# POWER.net
KiCad netlist of a schematic drawn in Altium Designer
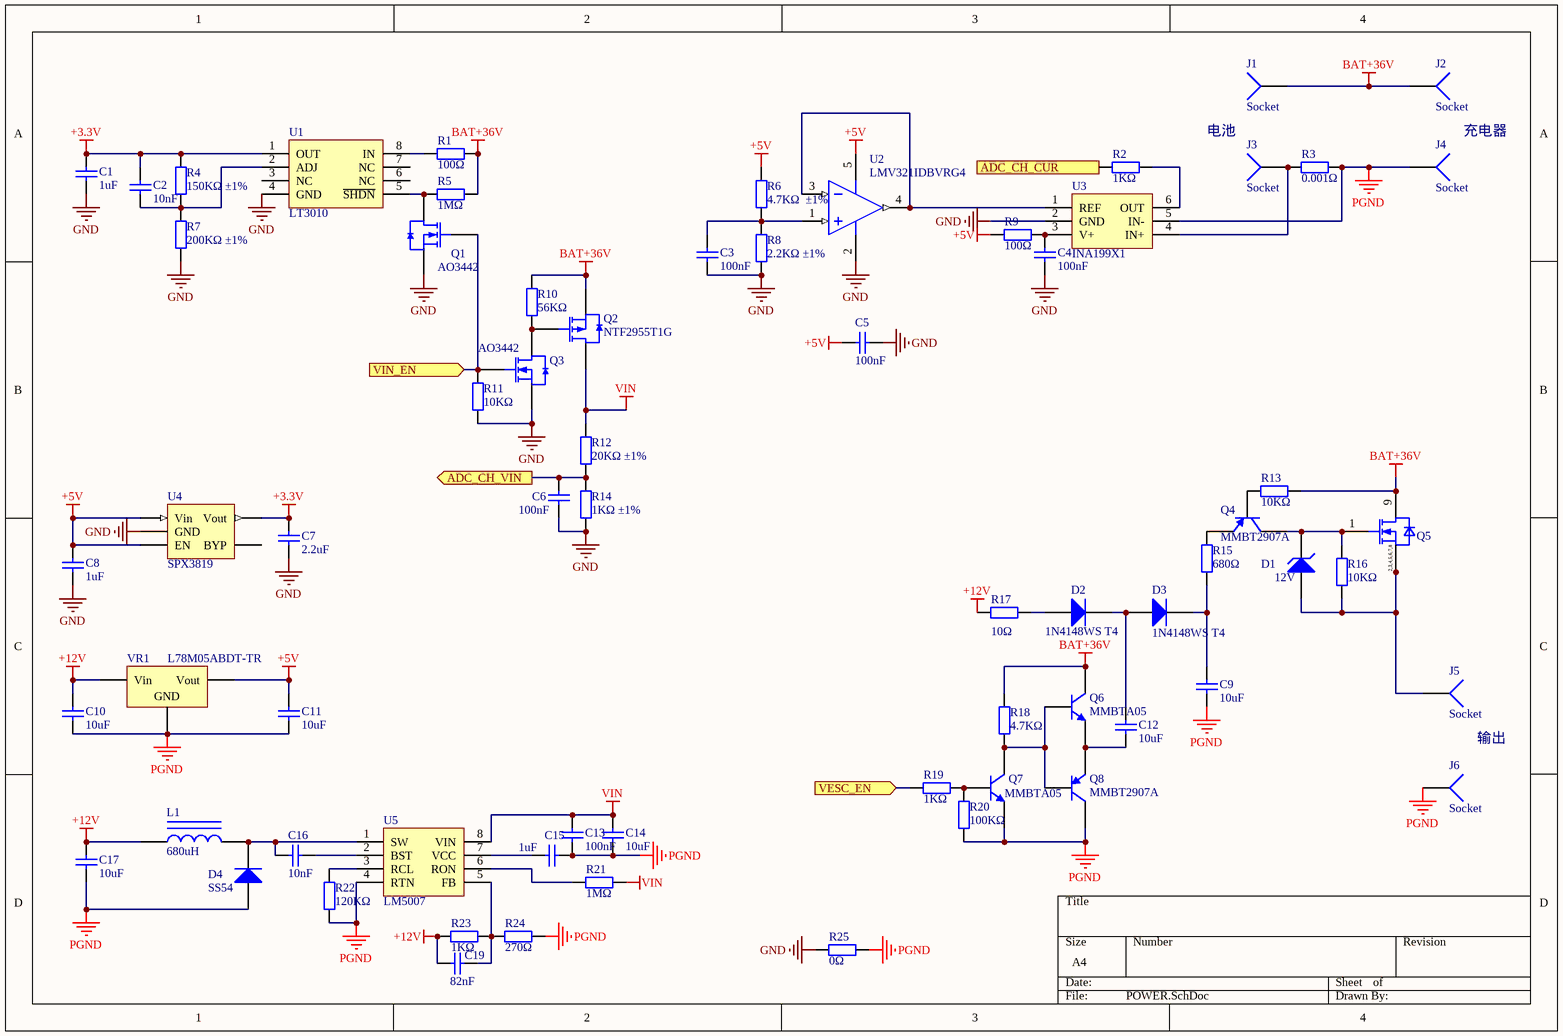
[diagram p0: POWER.SchDoc]

(export (version "E")
  (design (tool "Eeschema 10.0.6"))
  (components
    (comp (ref "C1")
      (value "1uF")
      (footprint "0603_C")
      (description "贴片电容")
      (libsource (lib "altium-import") (part "root_1_0603 1uF (105) 10% 50V_"))
    )
    (comp (ref "C2")
      (value "10nF")
      (footprint "0402_C")
      (description "贴片电容")
      (libsource (lib "Miscellaneous Devices LC") (part "0402 10nF (103) 10% 50V"))
    )
    (comp (ref "C3")
      (value "100nF")
      (footprint "0402_C")
      (description "贴片电容")
      (libsource (lib "Miscellaneous Devices LC") (part "0402 100nF (104) 10% 16V"))
    )
    (comp (ref "C4")
      (value "100nF")
      (footprint "0402_C")
      (description "贴片电容")
      (libsource (lib "Miscellaneous Devices LC") (part "0402 100nF (104) 10% 16V"))
    )
    (comp (ref "C5")
      (value "100nF")
      (footprint "0402_C")
      (description "贴片电容")
      (libsource (lib "Miscellaneous Devices LC") (part "0402 100nF (104) 10% 16V"))
    )
    (comp (ref "C6")
      (value "100nF")
      (footprint "0402_C")
      (description "贴片电容")
      (libsource (lib "Miscellaneous Devices LC") (part "0402 100nF (104) 10% 16V"))
    )
    (comp (ref "C7")
      (value "2.2uF")
      (footprint "0603_C")
      (description "贴片电容")
      (libsource (lib "altium-import") (part "root_1_0603 2.2uF (225) 10% 16V_"))
    )
    (comp (ref "C8")
      (value "1uF")
      (footprint "0603_C")
      (description "贴片电容")
      (libsource (lib "altium-import") (part "root_1_0603 1uF (105) 10% 50V_"))
    )
    (comp (ref "C9")
      (value "10uF")
      (footprint "0805_C")
      (description "贴片电容")
      (libsource (lib "Miscellaneous Devices LC") (part "0805 10uF (106) 10% 25V"))
    )
    (comp (ref "C10")
      (value "10uF")
      (footprint "0805_C")
      (description "贴片电容")
      (libsource (lib "Miscellaneous Devices LC") (part "0805 10uF (106) 10% 25V"))
    )
    (comp (ref "C11")
      (value "10uF")
      (footprint "0805_C")
      (description "贴片电容")
      (libsource (lib "Miscellaneous Devices LC") (part "0805 10uF (106) 10% 25V"))
    )
    (comp (ref "C12")
      (value "10uF")
      (footprint "0805_C")
      (description "贴片电容")
      (libsource (lib "Miscellaneous Devices LC") (part "0805 10uF (106) 10% 25V"))
    )
    (comp (ref "C13")
      (value "100nF")
      (footprint "0805_C")
      (description "贴片电容")
      (libsource (lib "altium-import") (part "root_1_0805 100nF(104) 10% 50V_"))
    )
    (comp (ref "C14")
      (value "10uF")
      (footprint "1206_C")
      (description "贴片电容")
      (libsource (lib "Miscellaneous Devices LC") (part "1206 10uF (106) 10% 50V"))
    )
    (comp (ref "C15")
      (value "1uF")
      (footprint "0402_C")
      (description "贴片电容")
      (libsource (lib "altium-import") (part "root_0_0603 1uF (105) 10% 50V_"))
    )
    (comp (ref "C16")
      (value "10nF")
      (footprint "0603_C")
      (description "贴片电容")
      (libsource (lib "Miscellaneous Devices LC") (part "0603 10nF (103) 10% 50V"))
    )
    (comp (ref "C17")
      (value "10uF")
      (footprint "1206_C")
      (description "贴片电容")
      (libsource (lib "Miscellaneous Devices LC") (part "1206 10uF (106) 10% 50V"))
    )
    (comp (ref "C19")
      (value "82nF")
      (footprint "0402_C")
      (description "贴片电容")
      (libsource (lib "altium-import") (part "root_0_0603 82pF (820) 5% 50V_"))
    )
    (comp (ref "D1")
      (value "12V")
      (footprint "LL-34")
      (description "稳压二极管")
      (libsource (lib "Miscellaneous Devices LC") (part "LL-34 ZMM5V6"))
    )
    (comp (ref "D2")
      (value "1N4148WS T4")
      (footprint "SOD-323")
      (description "二极管")
      (libsource (lib "Miscellaneous Devices LC") (part "SOD-323 1N4148WS T4"))
    )
    (comp (ref "D3")
      (value "1N4148WS T4")
      (footprint "SOD-323")
      (description "二极管")
      (libsource (lib "Miscellaneous Devices LC") (part "SOD-323 1N4148WS T4"))
    )
    (comp (ref "D4")
      (value "SS54")
      (footprint "SMA(DO-214AC)_S1")
      (description "二极管")
      (libsource (lib "altium-import") (part "root_1_SMA(DO-214AC) SS54_"))
    )
    (comp (ref "J1")
      (value "Socket")
      (footprint "PIN1")
      (fields (field (name "PUBLISHER") "Altium Limited"))
      (libsource (lib "Miscellaneous Connectors") (part "Socket"))
    )
    (comp (ref "J2")
      (value "Socket")
      (footprint "PIN1")
      (fields (field (name "PUBLISHER") "Altium Limited"))
      (libsource (lib "Miscellaneous Connectors") (part "Socket"))
    )
    (comp (ref "J3")
      (value "Socket")
      (footprint "PIN1")
      (fields (field (name "PUBLISHER") "Altium Limited"))
      (libsource (lib "Miscellaneous Connectors") (part "Socket"))
    )
    (comp (ref "J4")
      (value "Socket")
      (footprint "PIN1")
      (fields (field (name "PUBLISHER") "Altium Limited"))
      (libsource (lib "Miscellaneous Connectors") (part "Socket"))
    )
    (comp (ref "J5")
      (value "Socket")
      (footprint "PIN1")
      (fields (field (name "PUBLISHER") "Altium Limited"))
      (libsource (lib "Miscellaneous Connectors") (part "Socket"))
    )
    (comp (ref "J6")
      (value "Socket")
      (footprint "PIN1")
      (fields (field (name "PUBLISHER") "Altium Limited"))
      (libsource (lib "Miscellaneous Connectors") (part "Socket"))
    )
    (comp (ref "L1")
      (value "680uH")
      (footprint "CDRH74")
      (description "贴片电感")
      (libsource (lib "Miscellaneous Devices LC") (part "0805 10uH 10%"))
    )
    (comp (ref "Q1")
      (value "AO3442")
      (footprint "SOT-23-3L")
      (description "MOS(场效应管)")
      (libsource (lib "altium-import") (part "root_0_mirrored_AO3400A N道沟 X0YV1T SOT-23_"))
    )
    (comp (ref "Q2")
      (value "NTF2955T1G")
      (footprint "SOT-223")
      (description "MOS(场效应管)")
      (libsource (lib "altium-import") (part "root_2_mirrored_AO3401A P道沟 X13A15 SOT-23_"))
    )
    (comp (ref "Q3")
      (value "AO3442")
      (footprint "SOT-23-3L")
      (description "MOS(场效应管)")
      (libsource (lib "altium-import") (part "root_0_AO3400A N道沟 X0YV1T SOT-23_"))
    )
    (comp (ref "Q4")
      (value "MMBT2907A")
      (footprint "SOT-23(SOT-23-3)")
      (description "三极管")
      (libsource (lib "Miscellaneous Devices LC") (part "SOT-23 SS8550 Y2"))
    )
    (comp (ref "Q5")
      (value "IPT007N06N")
      (footprint "INF-PG-HSOF-8-1-0")
      (description "OptiMOS N-Channel Power-Transistor")
      (fields (field (name "MANUFACTURER") "Infineon Technologies"))
      (libsource (lib "altium-import") (part "root_0_IPT007N06N_"))
    )
    (comp (ref "Q6")
      (value "MMBTA05")
      (footprint "SOT-23(SOT-23-3)")
      (description "三极管")
      (libsource (lib "Miscellaneous Devices LC") (part "SOT-23 SS8050 Y1"))
    )
    (comp (ref "Q7")
      (value "MMBTA05")
      (footprint "SOT-23(SOT-23-3)")
      (description "三极管")
      (libsource (lib "Miscellaneous Devices LC") (part "SOT-23 SS8050 Y1"))
    )
    (comp (ref "Q8")
      (value "MMBT2907A")
      (footprint "SOT-23(SOT-23-3)")
      (description "三极管")
      (libsource (lib "Miscellaneous Devices LC") (part "SOT-23 SS8550 Y2"))
    )
    (comp (ref "R1")
      (value "100Ω")
      (footprint "0402_R")
      (description "贴片电阻")
      (libsource (lib "Miscellaneous Devices LC") (part "0402 100Ω (1000) 1%"))
    )
    (comp (ref "R2")
      (value "1KΩ")
      (footprint "0402_R")
      (description "贴片电阻")
      (libsource (lib "") (part "0402 1KΩ (1001) 1%_1"))
    )
    (comp (ref "R3")
      (value "0.001Ω")
      (footprint "2512_R")
      (description "贴片电阻")
      (libsource (lib "") (part "0603 0Ω (0R0) 1%_1"))
    )
    (comp (ref "R4")
      (value "150KΩ ±1%")
      (footprint "0402_R")
      (description "贴片电阻")
      (libsource (lib "Miscellaneous Devices LC") (part "0402 150KΩ (1503) 1%"))
    )
    (comp (ref "R5")
      (value "1MΩ")
      (footprint "0402_R")
      (description "贴片电阻")
      (libsource (lib "Miscellaneous Devices LC") (part "0402 1MΩ (1004) 1%"))
    )
    (comp (ref "R6")
      (value "4.7KΩ  ±1%")
      (footprint "0402_R")
      (description "贴片电阻")
      (libsource (lib "Miscellaneous Devices LC") (part "0402 4.7KΩ (4701) 1%"))
    )
    (comp (ref "R7")
      (value "200KΩ ±1%")
      (footprint "0402_R")
      (description "贴片电阻")
      (libsource (lib "Miscellaneous Devices LC") (part "0402 200KΩ (2003) 1%"))
    )
    (comp (ref "R8")
      (value "2.2KΩ ±1%")
      (footprint "0402_R")
      (description "贴片电阻")
      (libsource (lib "Miscellaneous Devices LC") (part "0402 2.2KΩ (2201) 1%"))
    )
    (comp (ref "R9")
      (value "100Ω")
      (footprint "0402_R")
      (description "贴片电阻")
      (libsource (lib "Miscellaneous Devices LC") (part "0402 100Ω (1000) 1%"))
    )
    (comp (ref "R10")
      (value "56KΩ")
      (footprint "0402_R")
      (description "贴片电阻")
      (libsource (lib "Miscellaneous Devices LC") (part "0402 56KΩ (5602) 1%"))
    )
    (comp (ref "R11")
      (value "10KΩ")
      (footprint "0402_R")
      (description "贴片电阻")
      (libsource (lib "Miscellaneous Devices LC") (part "0402 10KΩ (1002) 1%"))
    )
    (comp (ref "R12")
      (value "20KΩ ±1%")
      (footprint "0402_R")
      (description "贴片电阻")
      (libsource (lib "Miscellaneous Devices LC") (part "0402 20KΩ (2002) 1%"))
    )
    (comp (ref "R13")
      (value "10KΩ")
      (footprint "0603_R")
      (description "贴片电阻")
      (libsource (lib "Miscellaneous Devices LC") (part "0603 10KΩ (1002) 1%"))
    )
    (comp (ref "R14")
      (value "1KΩ ±1%")
      (footprint "0402_R")
      (description "贴片电阻")
      (libsource (lib "Miscellaneous Devices LC") (part "0402 1KΩ (1001) 1%"))
    )
    (comp (ref "R15")
      (value "680Ω")
      (footprint "0603_R")
      (description "贴片电阻")
      (libsource (lib "Miscellaneous Devices LC") (part "0603 680Ω (6800) 1%"))
    )
    (comp (ref "R16")
      (value "10KΩ")
      (footprint "0603_R")
      (description "贴片电阻")
      (libsource (lib "") (part "0603 10KΩ (1002) 1%_1"))
    )
    (comp (ref "R17")
      (value "10Ω")
      (footprint "0603_R")
      (description "贴片电阻")
      (libsource (lib "") (part "0603 680Ω (6800) 1%_1"))
    )
    (comp (ref "R18")
      (value "4.7KΩ")
      (footprint "0603_R")
      (description "贴片电阻")
      (libsource (lib "Miscellaneous Devices LC") (part "0603 4.7KΩ (4701) 1%"))
    )
    (comp (ref "R19")
      (value "1KΩ")
      (footprint "0603_R")
      (description "贴片电阻")
      (libsource (lib "Miscellaneous Devices LC") (part "0603 1KΩ (1001) 1%"))
    )
    (comp (ref "R20")
      (value "100KΩ")
      (footprint "0603_R")
      (description "贴片电阻")
      (libsource (lib "Miscellaneous Devices LC") (part "0603 30KΩ (3002) 1%"))
    )
    (comp (ref "R21")
      (value "1MΩ")
      (footprint "0402_R")
      (description "贴片电阻")
      (libsource (lib "Miscellaneous Devices LC") (part "0402 1MΩ (1004) 1%"))
    )
    (comp (ref "R22")
      (value "120KΩ")
      (footprint "0402_R")
      (description "贴片电阻")
      (libsource (lib "Miscellaneous Devices LC") (part "0402 120KΩ (1203) 1%"))
    )
    (comp (ref "R23")
      (value "1KΩ")
      (footprint "0402_R")
      (description "贴片电阻")
      (libsource (lib "") (part "0402 1KΩ (1001) 1%_1"))
    )
    (comp (ref "R24")
      (value "270Ω")
      (footprint "0402_R")
      (description "贴片电阻")
      (libsource (lib "altium-import") (part "root_0_0603 270Ω (2700) 1%_"))
    )
    (comp (ref "R25")
      (value "0Ω")
      (footprint "0603_R")
      (description "贴片电阻")
      (libsource (lib "Miscellaneous Devices LC") (part "0603 0Ω (0R0) 1%"))
    )
    (comp (ref "U1")
      (value "LT3010")
      (footprint "MSOP-8_EP")
      (description "50mA、3V 至 80V 低压差微功率稳压器")
      (libsource (lib "altium-import") (part "root_0_LT3010_"))
    )
    (comp (ref "U2")
      (value "LMV321IDBVRG4")
      (footprint "SOT-23-5")
      (description "运放")
      (libsource (lib "altium-import") (part "root_0_LMV321IDBVRG4_"))
    )
    (comp (ref "U3")
      (value "INA199X1")
      (footprint "DCK0006A_N")
      (libsource (lib "altium-import") (part "root_0_INA199X1_"))
    )
    (comp (ref "U4")
      (value "SPX3819")
      (footprint "SOT25-5")
      (libsource (lib "altium-import") (part "root_0_SPX3819_"))
    )
    (comp (ref "U5")
      (value "LM5007")
      (footprint "MSOP-8")
      (description "降压开关稳压器")
      (libsource (lib "altium-import") (part "root_0_LM5007_"))
    )
    (comp (ref "VR1")
      (value "L78M05ABDT-TR")
      (footprint "TO-252-2-180")
      (description "低压差线性稳压(LDO)")
      (libsource (lib "altium-import") (part "root_0_TO-252-2 L78M05ABDT-TR_"))
    )
  )
  (nets
    (net (code "1") (name "+3.3V") (class "Default")
      (node (ref "C1") (pin "2") (pinfunction "2_2") (pintype "passive"))
      (node (ref "C2") (pin "2") (pinfunction "2_2") (pintype "passive"))
      (node (ref "C7") (pin "2") (pinfunction "2_2") (pintype "passive"))
      (node (ref "R4") (pin "2") (pinfunction "2_2") (pintype "passive"))
      (node (ref "U1") (pin "1") (pinfunction "OUT_1") (pintype "passive"))
      (node (ref "U4") (pin "5") (pinfunction "Vout_5") (pintype "output"))
    )
    (net (code "2") (name "+5V") (class "Default")
      (node (ref "C11") (pin "2") (pinfunction "2_2") (pintype "passive"))
      (node (ref "C5") (pin "2") (pinfunction "2_2") (pintype "passive"))
      (node (ref "C8") (pin "2") (pinfunction "2_2") (pintype "passive"))
      (node (ref "R6") (pin "2") (pinfunction "2_2") (pintype "passive"))
      (node (ref "R9") (pin "1") (pinfunction "1_1") (pintype "passive"))
      (node (ref "U2") (pin "5") (pinfunction "V+_5") (pintype "power_in"))
      (node (ref "U4") (pin "1") (pinfunction "Vin_1") (pintype "input"))
      (node (ref "U4") (pin "3") (pinfunction "EN_3") (pintype "passive"))
      (node (ref "VR1") (pin "3") (pinfunction "Vout_3") (pintype "passive"))
    )
    (net (code "3") (name "+12V") (class "Default")
      (node (ref "C10") (pin "2") (pinfunction "2_2") (pintype "passive"))
      (node (ref "C17") (pin "1") (pinfunction "1_1") (pintype "passive"))
      (node (ref "C19") (pin "1") (pinfunction "1_1") (pintype "passive"))
      (node (ref "L1") (pin "1") (pinfunction "1_1") (pintype "passive"))
      (node (ref "R17") (pin "2") (pinfunction "2_2") (pintype "passive"))
      (node (ref "R23") (pin "1") (pinfunction "1_1") (pintype "passive"))
      (node (ref "VR1") (pin "1") (pinfunction "Vin_1") (pintype "passive"))
    )
    (net (code "4") (name "/ADC_CH_CUR") (class "Default")
      (node (ref "R2") (pin "1") (pinfunction "1_1") (pintype "passive"))
    )
    (net (code "5") (name "/ADC_CH_VIN") (class "Default")
      (node (ref "C6") (pin "2") (pinfunction "2_2") (pintype "passive"))
      (node (ref "R12") (pin "1") (pinfunction "1_1") (pintype "passive"))
      (node (ref "R14") (pin "2") (pinfunction "2_2") (pintype "passive"))
    )
    (net (code "6") (name "/VESC_EN") (class "Default")
      (node (ref "R19") (pin "1") (pinfunction "1_1") (pintype "passive"))
    )
    (net (code "7") (name "/VIN_EN") (class "Default")
      (node (ref "Q1") (pin "1") (pinfunction "G_1") (pintype "passive"))
      (node (ref "Q3") (pin "1") (pinfunction "G_1") (pintype "passive"))
      (node (ref "R11") (pin "2") (pinfunction "2_2") (pintype "passive"))
    )
    (net (code "8") (name "BAT+36V") (class "Default")
      (node (ref "J1") (pin "1") (pinfunction "1_1") (pintype "passive"))
      (node (ref "J2") (pin "1") (pinfunction "1_1") (pintype "passive"))
      (node (ref "Q2") (pin "3") (pinfunction "S_3") (pintype "passive"))
      (node (ref "Q5") (pin "9") (pinfunction "DRAIN_9") (pintype "passive"))
      (node (ref "Q6") (pin "3") (pinfunction "C_3") (pintype "passive"))
      (node (ref "R1") (pin "2") (pinfunction "2_2") (pintype "passive"))
      (node (ref "R10") (pin "2") (pinfunction "2_2") (pintype "passive"))
      (node (ref "R13") (pin "1") (pinfunction "1_1") (pintype "passive"))
      (node (ref "R18") (pin "2") (pinfunction "2_2") (pintype "passive"))
      (node (ref "R5") (pin "2") (pinfunction "2_2") (pintype "passive"))
    )
    (net (code "9") (name "GND") (class "Default")
      (node (ref "C1") (pin "1") (pinfunction "1_1") (pintype "passive"))
      (node (ref "C3") (pin "1") (pinfunction "1_1") (pintype "passive"))
      (node (ref "C4") (pin "1") (pinfunction "1_1") (pintype "passive"))
      (node (ref "C5") (pin "1") (pinfunction "1_1") (pintype "passive"))
      (node (ref "C6") (pin "1") (pinfunction "1_1") (pintype "passive"))
      (node (ref "C7") (pin "1") (pinfunction "1_1") (pintype "passive"))
      (node (ref "C8") (pin "1") (pinfunction "1_1") (pintype "passive"))
      (node (ref "Q1") (pin "2") (pinfunction "S_2") (pintype "passive"))
      (node (ref "Q3") (pin "2") (pinfunction "S_2") (pintype "passive"))
      (node (ref "R11") (pin "1") (pinfunction "1_1") (pintype "passive"))
      (node (ref "R14") (pin "1") (pinfunction "1_1") (pintype "passive"))
      (node (ref "R25") (pin "1") (pinfunction "1_1") (pintype "passive"))
      (node (ref "R7") (pin "1") (pinfunction "1_1") (pintype "passive"))
      (node (ref "R8") (pin "1") (pinfunction "1_1") (pintype "passive"))
      (node (ref "U1") (pin "4") (pinfunction "GND_4") (pintype "passive"))
      (node (ref "U2") (pin "2") (pinfunction "V-_2") (pintype "power_in"))
      (node (ref "U3") (pin "2") (pinfunction "GND_2") (pintype "passive"))
      (node (ref "U4") (pin "2") (pinfunction "GND_2") (pintype "passive"))
    )
    (net (code "10") (name "Net-(D1-A)") (class "Default")
      (node (ref "D1") (pin "1") (pinfunction "A_1") (pintype "passive"))
      (node (ref "J5") (pin "1") (pinfunction "1_1") (pintype "passive"))
      (node (ref "Q5") (pin "2") (pinfunction "SOURCE_2") (pintype "passive"))
      (node (ref "Q5") (pin "3") (pinfunction "SOURCE_3") (pintype "passive"))
      (node (ref "Q5") (pin "4") (pinfunction "SOURCE_4") (pintype "passive"))
      (node (ref "Q5") (pin "5") (pinfunction "SOURCE_5") (pintype "passive"))
      (node (ref "Q5") (pin "6") (pinfunction "SOURCE_6") (pintype "passive"))
      (node (ref "Q5") (pin "7") (pinfunction "SOURCE_7") (pintype "passive"))
      (node (ref "Q5") (pin "8") (pinfunction "SOURCE_8") (pintype "passive"))
      (node (ref "R16") (pin "1") (pinfunction "1_1") (pintype "passive"))
    )
    (net (code "11") (name "Net-(D1-K)") (class "Default")
      (node (ref "D1") (pin "2") (pinfunction "K_2") (pintype "passive"))
      (node (ref "Q4") (pin "3") (pinfunction "C_3") (pintype "passive"))
      (node (ref "Q5") (pin "1") (pinfunction "GATE_1") (pintype "passive"))
      (node (ref "R16") (pin "2") (pinfunction "2_2") (pintype "passive"))
    )
    (net (code "12") (name "Net-(D2-A)") (class "Default")
      (node (ref "D2") (pin "1") (pinfunction "A_1") (pintype "passive"))
      (node (ref "R17") (pin "1") (pinfunction "1_1") (pintype "passive"))
    )
    (net (code "13") (name "Net-(D2-K)") (class "Default")
      (node (ref "C12") (pin "2") (pinfunction "2_2") (pintype "passive"))
      (node (ref "D2") (pin "2") (pinfunction "K_2") (pintype "passive"))
      (node (ref "D3") (pin "1") (pinfunction "A_1") (pintype "passive"))
    )
    (net (code "14") (name "Net-(D3-K)") (class "Default")
      (node (ref "C9") (pin "2") (pinfunction "2_2") (pintype "passive"))
      (node (ref "D3") (pin "2") (pinfunction "K_2") (pintype "passive"))
      (node (ref "R15") (pin "2") (pinfunction "2_2") (pintype "passive"))
    )
    (net (code "15") (name "Net-(D4-K)") (class "Default")
      (node (ref "C16") (pin "1") (pinfunction "1_1") (pintype "passive"))
      (node (ref "D4") (pin "2") (pinfunction "K_2") (pintype "passive"))
      (node (ref "L1") (pin "2") (pinfunction "2_2") (pintype "passive"))
      (node (ref "U5") (pin "1") (pinfunction "SW_1") (pintype "passive"))
    )
    (net (code "16") (name "Net-(Q1-D)") (class "Default")
      (node (ref "Q1") (pin "3") (pinfunction "D_3") (pintype "passive"))
      (node (ref "R5") (pin "1") (pinfunction "1_1") (pintype "passive"))
      (node (ref "U1") (pin "5") (pinfunction "~{SHDN}_5") (pintype "passive"))
    )
    (net (code "17") (name "Net-(Q2-G)") (class "Default")
      (node (ref "Q2") (pin "1") (pinfunction "G_1") (pintype "passive"))
      (node (ref "Q3") (pin "3") (pinfunction "D_3") (pintype "passive"))
      (node (ref "R10") (pin "1") (pinfunction "1_1") (pintype "passive"))
    )
    (net (code "18") (name "Net-(Q4-B)") (class "Default")
      (node (ref "Q4") (pin "1") (pinfunction "B_1") (pintype "passive"))
      (node (ref "R13") (pin "2") (pinfunction "2_2") (pintype "passive"))
    )
    (net (code "19") (name "Net-(Q4-E)") (class "Default")
      (node (ref "Q4") (pin "2") (pinfunction "E_2") (pintype "passive"))
      (node (ref "R15") (pin "1") (pinfunction "1_1") (pintype "passive"))
    )
    (net (code "20") (name "Net-(Q6-B)") (class "Default")
      (node (ref "Q6") (pin "1") (pinfunction "B_1") (pintype "passive"))
      (node (ref "Q7") (pin "3") (pinfunction "C_3") (pintype "passive"))
      (node (ref "Q8") (pin "1") (pinfunction "B_1") (pintype "passive"))
      (node (ref "R18") (pin "1") (pinfunction "1_1") (pintype "passive"))
    )
    (net (code "21") (name "Net-(Q6-E)") (class "Default")
      (node (ref "C12") (pin "1") (pinfunction "1_1") (pintype "passive"))
      (node (ref "Q6") (pin "2") (pinfunction "E_2") (pintype "passive"))
      (node (ref "Q8") (pin "2") (pinfunction "E_2") (pintype "passive"))
    )
    (net (code "22") (name "Net-(Q7-B)") (class "Default")
      (node (ref "Q7") (pin "1") (pinfunction "B_1") (pintype "passive"))
      (node (ref "R19") (pin "2") (pinfunction "2_2") (pintype "passive"))
      (node (ref "R20") (pin "2") (pinfunction "2_2") (pintype "passive"))
    )
    (net (code "23") (name "Net-(U1-ADJ)") (class "Default")
      (node (ref "C2") (pin "1") (pinfunction "1_1") (pintype "passive"))
      (node (ref "R4") (pin "1") (pinfunction "1_1") (pintype "passive"))
      (node (ref "R7") (pin "2") (pinfunction "2_2") (pintype "passive"))
      (node (ref "U1") (pin "2") (pinfunction "ADJ_2") (pintype "passive"))
    )
    (net (code "24") (name "Net-(U1-IN)") (class "Default")
      (node (ref "R1") (pin "1") (pinfunction "1_1") (pintype "passive"))
      (node (ref "U1") (pin "8") (pinfunction "IN_8") (pintype "passive"))
    )
    (net (code "25") (name "Net-(U2-IN+)") (class "Default")
      (node (ref "C3") (pin "2") (pinfunction "2_2") (pintype "passive"))
      (node (ref "R6") (pin "1") (pinfunction "1_1") (pintype "passive"))
      (node (ref "R8") (pin "2") (pinfunction "2_2") (pintype "passive"))
      (node (ref "U2") (pin "1") (pinfunction "IN+_1") (pintype "input"))
    )
    (net (code "26") (name "Net-(U2-IN-)") (class "Default")
      (node (ref "U2") (pin "3") (pinfunction "IN-_3") (pintype "input"))
      (node (ref "U2") (pin "4") (pinfunction "OUT_4") (pintype "output"))
      (node (ref "U3") (pin "1") (pinfunction "REF_1") (pintype "passive"))
    )
    (net (code "27") (name "Net-(U3-IN+)") (class "Default")
      (node (ref "J3") (pin "1") (pinfunction "1_1") (pintype "passive"))
      (node (ref "R3") (pin "2") (pinfunction "2_2") (pintype "passive"))
      (node (ref "U3") (pin "4") (pinfunction "IN+_4") (pintype "passive"))
    )
    (net (code "28") (name "Net-(U3-OUT)") (class "Default")
      (node (ref "R2") (pin "2") (pinfunction "2_2") (pintype "passive"))
      (node (ref "U3") (pin "6") (pinfunction "OUT_6") (pintype "passive"))
    )
    (net (code "29") (name "Net-(U3-V+)") (class "Default")
      (node (ref "C4") (pin "2") (pinfunction "2_2") (pintype "passive"))
      (node (ref "R9") (pin "2") (pinfunction "2_2") (pintype "passive"))
      (node (ref "U3") (pin "3") (pinfunction "V+_3") (pintype "passive"))
    )
    (net (code "30") (name "Net-(U5-BST)") (class "Default")
      (node (ref "C16") (pin "2") (pinfunction "2_2") (pintype "passive"))
      (node (ref "U5") (pin "2") (pinfunction "BST_2") (pintype "passive"))
    )
    (net (code "31") (name "Net-(U5-FB)") (class "Default")
      (node (ref "C19") (pin "2") (pinfunction "2_2") (pintype "passive"))
      (node (ref "R23") (pin "2") (pinfunction "2_2") (pintype "passive"))
      (node (ref "R24") (pin "1") (pinfunction "1_1") (pintype "passive"))
      (node (ref "U5") (pin "5") (pinfunction "FB_5") (pintype "passive"))
    )
    (net (code "32") (name "Net-(U5-RCL)") (class "Default")
      (node (ref "R22") (pin "2") (pinfunction "2_2") (pintype "passive"))
      (node (ref "U5") (pin "3") (pinfunction "RCL_3") (pintype "passive"))
    )
    (net (code "33") (name "Net-(U5-RON)") (class "Default")
      (node (ref "R21") (pin "1") (pinfunction "1_1") (pintype "passive"))
      (node (ref "U5") (pin "6") (pinfunction "RON_6") (pintype "passive"))
    )
    (net (code "34") (name "Net-(U5-VCC)") (class "Default")
      (node (ref "C15") (pin "1") (pinfunction "1_1") (pintype "passive"))
      (node (ref "U5") (pin "7") (pinfunction "VCC_7") (pintype "passive"))
    )
    (net (code "35") (name "PGND") (class "Default")
      (node (ref "C10") (pin "1") (pinfunction "1_1") (pintype "passive"))
      (node (ref "C11") (pin "1") (pinfunction "1_1") (pintype "passive"))
      (node (ref "C13") (pin "1") (pinfunction "1_1") (pintype "passive"))
      (node (ref "C14") (pin "2") (pinfunction "2_2") (pintype "passive"))
      (node (ref "C15") (pin "2") (pinfunction "2_2") (pintype "passive"))
      (node (ref "C17") (pin "2") (pinfunction "2_2") (pintype "passive"))
      (node (ref "C9") (pin "1") (pinfunction "1_1") (pintype "passive"))
      (node (ref "D4") (pin "1") (pinfunction "A_1") (pintype "passive"))
      (node (ref "J4") (pin "1") (pinfunction "1_1") (pintype "passive"))
      (node (ref "J6") (pin "1") (pinfunction "1_1") (pintype "passive"))
      (node (ref "Q7") (pin "2") (pinfunction "E_2") (pintype "passive"))
      (node (ref "Q8") (pin "3") (pinfunction "C_3") (pintype "passive"))
      (node (ref "R20") (pin "1") (pinfunction "1_1") (pintype "passive"))
      (node (ref "R22") (pin "1") (pinfunction "1_1") (pintype "passive"))
      (node (ref "R24") (pin "2") (pinfunction "2_2") (pintype "passive"))
      (node (ref "R25") (pin "2") (pinfunction "2_2") (pintype "passive"))
      (node (ref "R3") (pin "1") (pinfunction "1_1") (pintype "passive"))
      (node (ref "U3") (pin "5") (pinfunction "IN-_5") (pintype "passive"))
      (node (ref "U5") (pin "4") (pinfunction "RTN_4") (pintype "passive"))
      (node (ref "VR1") (pin "2") (pinfunction "GND_2") (pintype "passive"))
    )
    (net (code "36") (name "VIN") (class "Default")
      (node (ref "C13") (pin "2") (pinfunction "2_2") (pintype "passive"))
      (node (ref "C14") (pin "1") (pinfunction "1_1") (pintype "passive"))
      (node (ref "Q2") (pin "2") (pinfunction "D_2") (pintype "passive"))
      (node (ref "R12") (pin "2") (pinfunction "2_2") (pintype "passive"))
      (node (ref "R21") (pin "2") (pinfunction "2_2") (pintype "passive"))
      (node (ref "U5") (pin "8") (pinfunction "VIN_8") (pintype "passive"))
    )
    (net (code "37") (name "unconnected-(U1-NC-Pad3)") (class "Default")
      (node (ref "U1") (pin "3") (pinfunction "NC_3") (pintype "passive"))
    )
    (net (code "38") (name "unconnected-(U1-NC-Pad6)") (class "Default")
      (node (ref "U1") (pin "6") (pinfunction "NC_6") (pintype "passive"))
    )
    (net (code "39") (name "unconnected-(U1-NC-Pad7)") (class "Default")
      (node (ref "U1") (pin "7") (pinfunction "NC_7") (pintype "passive"))
    )
    (net (code "40") (name "unconnected-(U4-BYP-Pad4)") (class "Default")
      (node (ref "U4") (pin "4") (pinfunction "BYP_4") (pintype "passive"))
    )
  )
)
